# connector.net
KiCad netlist of a schematic drawn in Altium Designer
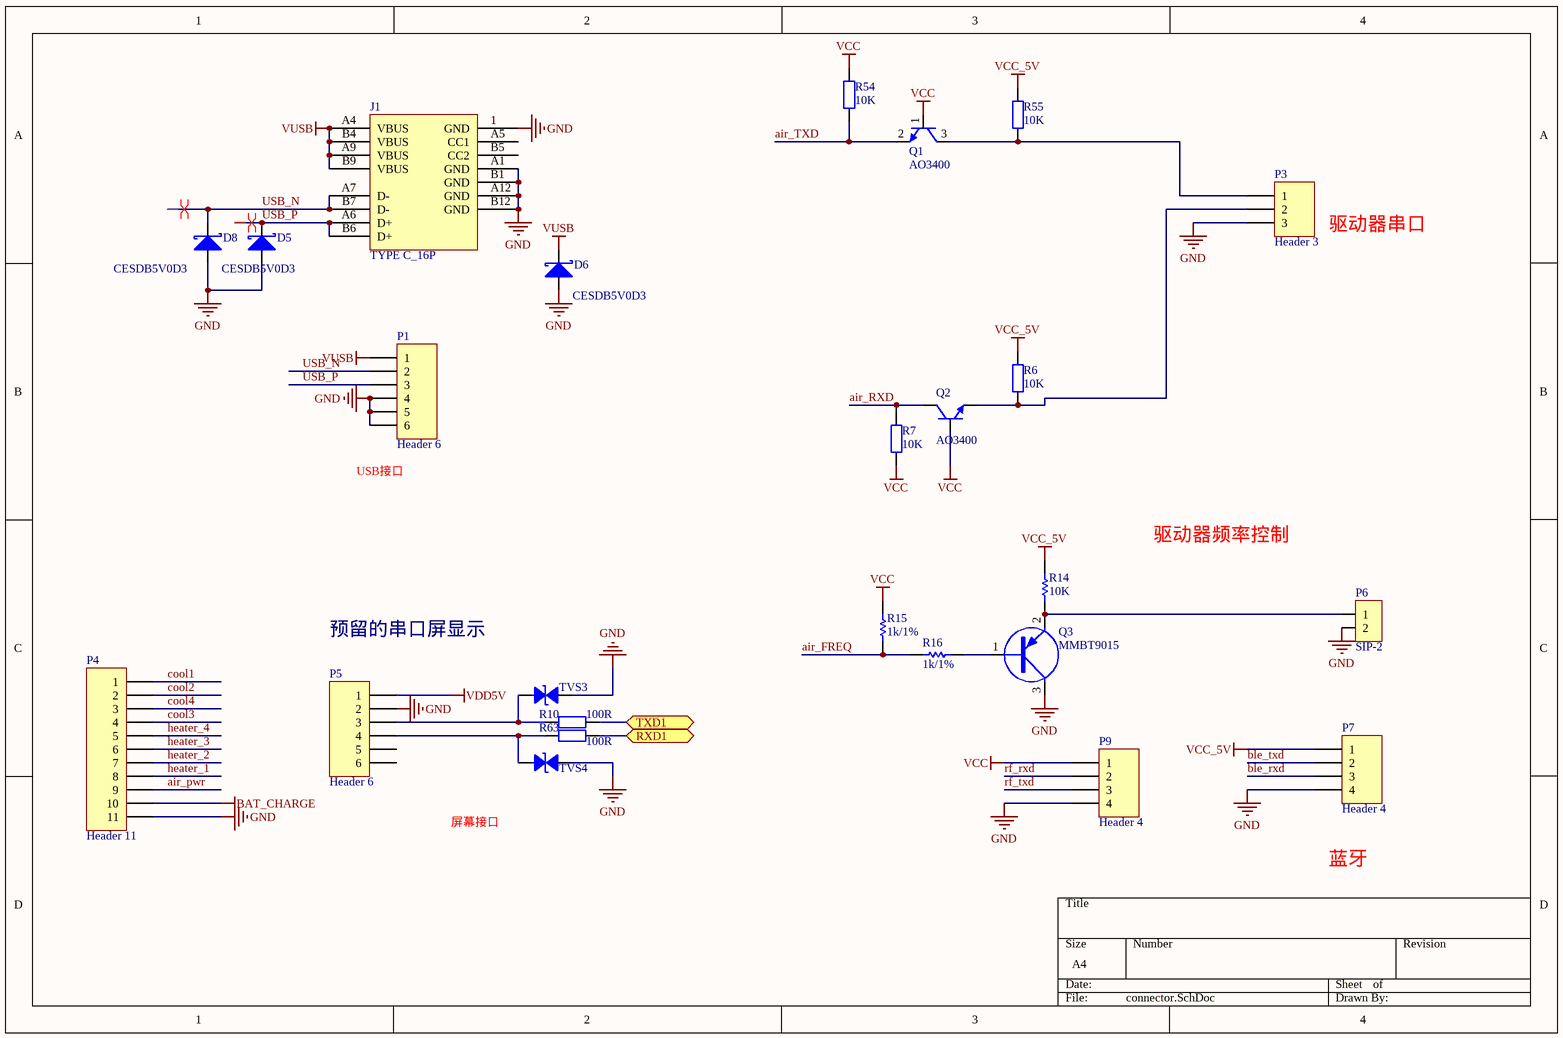
[diagram p0: connector.SchDoc]

(export (version "E")
  (design (tool "Eeschema 10.0.6"))
  (components
    (comp (ref "D5")
      (value "CESDB5V0D3")
      (footprint "SOD323")
      (description "Schottky Diode")
      (libsource (lib "*") (part "DIODE S"))
    )
    (comp (ref "D6")
      (value "CESDB5V0D3")
      (footprint "SOD323")
      (description "Schottky Diode")
      (libsource (lib "*") (part "DIODE S"))
    )
    (comp (ref "D8")
      (value "CESDB5V0D3")
      (footprint "SOD323")
      (description "Schottky Diode")
      (libsource (lib "*") (part "DIODE S"))
    )
    (comp (ref "J1")
      (value "TYPE C_16P")
      (footprint "TYPEC_16P")
      (libsource (lib "Schlib_20110825") (part "TYPE C_16P"))
    )
    (comp (ref "P1")
      (value "Header 6")
      (footprint "USB-A")
      (description "Header, 6-Pin")
      (fields (field (name "PUBLISHER") "Altium Limited"))
      (libsource (lib "Miscellaneous Connectors") (part "Header 6"))
    )
    (comp (ref "P3")
      (value "Header 3")
      (footprint "3X2.54MMZ")
      (description "Header, 3-Pin")
      (fields (field (name "PUBLISHER") "Altium Limited"))
      (libsource (lib "Miscellaneous Connectors") (part "Header 3"))
    )
    (comp (ref "P4")
      (value "Header 11")
      (footprint "12X2MMZ")
      (description "Header, 11-Pin")
      (fields (field (name "PUBLISHER") "Altium Limited"))
      (libsource (lib "Miscellaneous Connectors") (part "Header 11"))
    )
    (comp (ref "P5")
      (value "Header 6")
      (footprint "6X2MMZ")
      (description "Header, 6-Pin")
      (fields (field (name "PUBLISHER") "Altium Limited"))
      (libsource (lib "") (part "Header 6_1"))
    )
    (comp (ref "P6")
      (value "SIP-2")
      (footprint "SIP-2A")
      (description "XH2.54 2P 立贴")
      (libsource (lib "XiaoyI") (part "SIP-2"))
    )
    (comp (ref "P7")
      (value "Header 4")
      (footprint "4X2.54MMZ")
      (description "Header, 4-Pin")
      (fields (field (name "PUBLISHER") "Altium Limited"))
      (libsource (lib "Miscellaneous Connectors") (part "Header 4"))
    )
    (comp (ref "P9")
      (value "Header 4")
      (footprint "4X2.54MMZ")
      (description "Header, 4-Pin")
      (fields (field (name "PUBLISHER") "Altium Limited"))
      (libsource (lib "Miscellaneous Connectors") (part "Header 4"))
    )
    (comp (ref "Q1")
      (value "AO3400")
      (footprint "SOT-23")
      (description "NPN")
      (libsource (lib "XiaoyI") (part "NPN-1"))
    )
    (comp (ref "Q2")
      (value "AO3400")
      (footprint "SOT-23")
      (description "NPN")
      (libsource (lib "") (part "NPN-1_1"))
    )
    (comp (ref "Q3") (value "MMBT9015") (footprint "SOT23-3") (libsource (lib "Schlib1") (part "PNP")))
    (comp (ref "R6")
      (value "10K")
      (footprint "0603r")
      (description "贴片电阻 1%")
      (libsource (lib "XiaoyI") (part "RES2"))
    )
    (comp (ref "R7")
      (value "10K")
      (footprint "0603r")
      (description "贴片电阻 1%")
      (libsource (lib "XiaoyI") (part "RES2"))
    )
    (comp (ref "R10")
      (value "100R")
      (footprint "0603R")
      (description "贴片电阻 5%")
      (libsource (lib "") (part "RES2_1"))
    )
    (comp (ref "R14")
      (value "10K")
      (footprint "0603R")
      (description "Resistor")
      (fields (field (name "PUBLISHER") "Altium Limited"))
      (libsource (lib "Miscellaneous Devices") (part "Res1"))
    )
    (comp (ref "R15")
      (value "1k/1%")
      (footprint "0603R")
      (description "Resistor")
      (fields (field (name "PUBLISHER") "Altium Limited"))
      (libsource (lib "Miscellaneous Devices") (part "Res1"))
    )
    (comp (ref "R16")
      (value "1k/1%")
      (footprint "0603R")
      (description "Resistor")
      (fields (field (name "PUBLISHER") "Altium Limited"))
      (libsource (lib "Miscellaneous Devices") (part "Res1"))
    )
    (comp (ref "R54")
      (value "10K")
      (footprint "0603r")
      (description "贴片电阻 1%")
      (libsource (lib "XiaoyI") (part "RES2"))
    )
    (comp (ref "R55")
      (value "10K")
      (footprint "0603r")
      (description "贴片电阻 1%")
      (libsource (lib "XiaoyI") (part "RES2"))
    )
    (comp (ref "R63")
      (value "100R")
      (footprint "0603R")
      (description "贴片电阻 5%")
      (libsource (lib "") (part "RES2_1"))
    )
    (comp (ref "TVS3")
      (value "ESD5Z5.0CT1G")
      (footprint "SOD-523")
      (description "TVS")
      (libsource (lib "XiaoyI") (part "TVS-1"))
    )
    (comp (ref "TVS4")
      (value "ESD5Z5.0CT1G")
      (footprint "SOD-523")
      (description "TVS")
      (libsource (lib "XiaoyI") (part "TVS-1"))
    )
  )
  (nets
    (net (code "1") (name "/RXD1") (class "Default")
      (node (ref "R63") (pin "2") (pinfunction "2_2") (pintype "passive"))
    )
    (net (code "2") (name "/TXD1") (class "Default")
      (node (ref "R10") (pin "2") (pinfunction "2_2") (pintype "passive"))
    )
    (net (code "3") (name "/USB_N") (class "Default")
      (node (ref "D8") (pin "2") (pinfunction "K_2") (pintype "passive"))
      (node (ref "J1") (pin "A7") (pinfunction "D-_A7") (pintype "passive"))
      (node (ref "J1") (pin "B7") (pinfunction "D-_B7") (pintype "passive"))
      (node (ref "P1") (pin "2") (pinfunction "2_2") (pintype "passive"))
    )
    (net (code "4") (name "/USB_P") (class "Default")
      (node (ref "D5") (pin "2") (pinfunction "K_2") (pintype "passive"))
      (node (ref "J1") (pin "A6") (pinfunction "D+_A6") (pintype "passive"))
      (node (ref "J1") (pin "B6") (pinfunction "D+_B6") (pintype "passive"))
      (node (ref "P1") (pin "3") (pinfunction "3_3") (pintype "passive"))
    )
    (net (code "5") (name "/air_FREQ") (class "Default")
      (node (ref "R15") (pin "2") (pinfunction "2_2") (pintype "passive"))
      (node (ref "R16") (pin "2") (pinfunction "2_2") (pintype "passive"))
    )
    (net (code "6") (name "/air_RXD") (class "Default")
      (node (ref "Q2") (pin "3") (pinfunction "C_3") (pintype "passive"))
      (node (ref "R7") (pin "2") (pinfunction "2_2") (pintype "passive"))
    )
    (net (code "7") (name "/air_TXD") (class "Default")
      (node (ref "Q1") (pin "2") (pinfunction "E_2") (pintype "passive"))
      (node (ref "R54") (pin "1") (pinfunction "1_1") (pintype "passive"))
    )
    (net (code "8") (name "/air_pwr") (class "Default")
      (node (ref "P4") (pin "9") (pinfunction "9_9") (pintype "passive"))
    )
    (net (code "9") (name "/ble_rxd") (class "Default")
      (node (ref "P7") (pin "3") (pinfunction "3_3") (pintype "passive"))
    )
    (net (code "10") (name "/ble_txd") (class "Default")
      (node (ref "P7") (pin "2") (pinfunction "2_2") (pintype "passive"))
    )
    (net (code "11") (name "/cool1") (class "Default")
      (node (ref "P4") (pin "1") (pinfunction "1_1") (pintype "passive"))
    )
    (net (code "12") (name "/cool2") (class "Default")
      (node (ref "P4") (pin "2") (pinfunction "2_2") (pintype "passive"))
    )
    (net (code "13") (name "/cool3") (class "Default")
      (node (ref "P4") (pin "4") (pinfunction "4_4") (pintype "passive"))
    )
    (net (code "14") (name "/cool4") (class "Default")
      (node (ref "P4") (pin "3") (pinfunction "3_3") (pintype "passive"))
    )
    (net (code "15") (name "/heater_1") (class "Default")
      (node (ref "P4") (pin "8") (pinfunction "8_8") (pintype "passive"))
    )
    (net (code "16") (name "/heater_2") (class "Default")
      (node (ref "P4") (pin "7") (pinfunction "7_7") (pintype "passive"))
    )
    (net (code "17") (name "/heater_3") (class "Default")
      (node (ref "P4") (pin "6") (pinfunction "6_6") (pintype "passive"))
    )
    (net (code "18") (name "/heater_4") (class "Default")
      (node (ref "P4") (pin "5") (pinfunction "5_5") (pintype "passive"))
    )
    (net (code "19") (name "/rf_rxd") (class "Default")
      (node (ref "P9") (pin "2") (pinfunction "2_2") (pintype "passive"))
    )
    (net (code "20") (name "/rf_txd") (class "Default")
      (node (ref "P9") (pin "3") (pinfunction "3_3") (pintype "passive"))
    )
    (net (code "21") (name "BAT_CHARGE") (class "Default")
      (node (ref "P4") (pin "10") (pinfunction "10_10") (pintype "passive"))
    )
    (net (code "22") (name "GND") (class "Default")
      (node (ref "D5") (pin "1") (pinfunction "A_1") (pintype "passive"))
      (node (ref "D6") (pin "1") (pinfunction "A_1") (pintype "passive"))
      (node (ref "D8") (pin "1") (pinfunction "A_1") (pintype "passive"))
      (node (ref "J1") (pin "1") (pinfunction "GND_1") (pintype "passive"))
      (node (ref "J1") (pin "A1") (pinfunction "GND_A1") (pintype "passive"))
      (node (ref "J1") (pin "A12") (pinfunction "GND_A12") (pintype "passive"))
      (node (ref "J1") (pin "B1") (pinfunction "GND_B1") (pintype "passive"))
      (node (ref "J1") (pin "B12") (pinfunction "GND_B12") (pintype "passive"))
      (node (ref "P1") (pin "4") (pinfunction "4_4") (pintype "passive"))
      (node (ref "P1") (pin "5") (pinfunction "5_5") (pintype "passive"))
      (node (ref "P1") (pin "6") (pinfunction "6_6") (pintype "passive"))
      (node (ref "P3") (pin "3") (pinfunction "3_3") (pintype "passive"))
      (node (ref "P4") (pin "11") (pinfunction "11_11") (pintype "passive"))
      (node (ref "P5") (pin "2") (pinfunction "2_2") (pintype "passive"))
      (node (ref "P6") (pin "2") (pinfunction "2_2") (pintype "passive"))
      (node (ref "P7") (pin "4") (pinfunction "4_4") (pintype "passive"))
      (node (ref "P9") (pin "4") (pinfunction "4_4") (pintype "passive"))
      (node (ref "Q3") (pin "3") (pinfunction "C_3") (pintype "passive"))
      (node (ref "TVS3") (pin "1") (pinfunction "A_1") (pintype "passive"))
      (node (ref "TVS4") (pin "1") (pinfunction "A_1") (pintype "passive"))
    )
    (net (code "23") (name "Net-(Q1-C)") (class "Default")
      (node (ref "P3") (pin "1") (pinfunction "1_1") (pintype "passive"))
      (node (ref "Q1") (pin "3") (pinfunction "C_3") (pintype "passive"))
      (node (ref "R55") (pin "1") (pinfunction "1_1") (pintype "passive"))
    )
    (net (code "24") (name "Net-(Q2-E)") (class "Default")
      (node (ref "P3") (pin "2") (pinfunction "2_2") (pintype "passive"))
      (node (ref "Q2") (pin "2") (pinfunction "E_2") (pintype "passive"))
      (node (ref "R6") (pin "1") (pinfunction "1_1") (pintype "passive"))
    )
    (net (code "25") (name "Net-(Q3-B)") (class "Default")
      (node (ref "Q3") (pin "1") (pinfunction "B_1") (pintype "passive"))
      (node (ref "R16") (pin "1") (pinfunction "1_1") (pintype "passive"))
    )
    (net (code "26") (name "Net-(Q3-E)") (class "Default")
      (node (ref "P6") (pin "1") (pinfunction "1_1") (pintype "passive"))
      (node (ref "Q3") (pin "2") (pinfunction "E_2") (pintype "passive"))
      (node (ref "R14") (pin "1") (pinfunction "1_1") (pintype "passive"))
    )
    (net (code "27") (name "Net-(TVS3-B)") (class "Default")
      (node (ref "P5") (pin "3") (pinfunction "3_3") (pintype "passive"))
      (node (ref "R10") (pin "1") (pinfunction "1_1") (pintype "passive"))
      (node (ref "TVS3") (pin "2") (pinfunction "B_2") (pintype "passive"))
    )
    (net (code "28") (name "Net-(TVS4-B)") (class "Default")
      (node (ref "P5") (pin "4") (pinfunction "4_4") (pintype "passive"))
      (node (ref "R63") (pin "1") (pinfunction "1_1") (pintype "passive"))
      (node (ref "TVS4") (pin "2") (pinfunction "B_2") (pintype "passive"))
    )
    (net (code "29") (name "VCC") (class "Default")
      (node (ref "P9") (pin "1") (pinfunction "1_1") (pintype "passive"))
      (node (ref "Q1") (pin "1") (pinfunction "B_1") (pintype "passive"))
      (node (ref "Q2") (pin "1") (pinfunction "B_1") (pintype "passive"))
      (node (ref "R15") (pin "1") (pinfunction "1_1") (pintype "passive"))
      (node (ref "R54") (pin "2") (pinfunction "2_2") (pintype "passive"))
      (node (ref "R7") (pin "1") (pinfunction "1_1") (pintype "passive"))
    )
    (net (code "30") (name "VCC_5V") (class "Default")
      (node (ref "P7") (pin "1") (pinfunction "1_1") (pintype "passive"))
      (node (ref "R14") (pin "2") (pinfunction "2_2") (pintype "passive"))
      (node (ref "R55") (pin "2") (pinfunction "2_2") (pintype "passive"))
      (node (ref "R6") (pin "2") (pinfunction "2_2") (pintype "passive"))
    )
    (net (code "31") (name "VDD5V") (class "Default")
      (node (ref "P5") (pin "1") (pinfunction "1_1") (pintype "passive"))
    )
    (net (code "32") (name "VUSB") (class "Default")
      (node (ref "D6") (pin "2") (pinfunction "K_2") (pintype "passive"))
      (node (ref "J1") (pin "A4") (pinfunction "VBUS_A4") (pintype "passive"))
      (node (ref "J1") (pin "A9") (pinfunction "VBUS_A9") (pintype "passive"))
      (node (ref "J1") (pin "B4") (pinfunction "VBUS_B4") (pintype "passive"))
      (node (ref "J1") (pin "B9") (pinfunction "VBUS_B9") (pintype "passive"))
      (node (ref "P1") (pin "1") (pinfunction "1_1") (pintype "passive"))
    )
    (net (code "33") (name "unconnected-(J1-CC1-PadA5)") (class "Default")
      (node (ref "J1") (pin "A5") (pinfunction "CC1_A5") (pintype "passive"))
    )
    (net (code "34") (name "unconnected-(J1-CC2-PadB5)") (class "Default")
      (node (ref "J1") (pin "B5") (pinfunction "CC2_B5") (pintype "passive"))
    )
    (net (code "35") (name "unconnected-(P5-Pad5)") (class "Default")
      (node (ref "P5") (pin "5") (pinfunction "5_5") (pintype "passive"))
    )
    (net (code "36") (name "unconnected-(P5-Pad6)") (class "Default")
      (node (ref "P5") (pin "6") (pinfunction "6_6") (pintype "passive"))
    )
  )
)
